# Final_Project.net
KiCad netlist of a schematic drawn in EAGLE
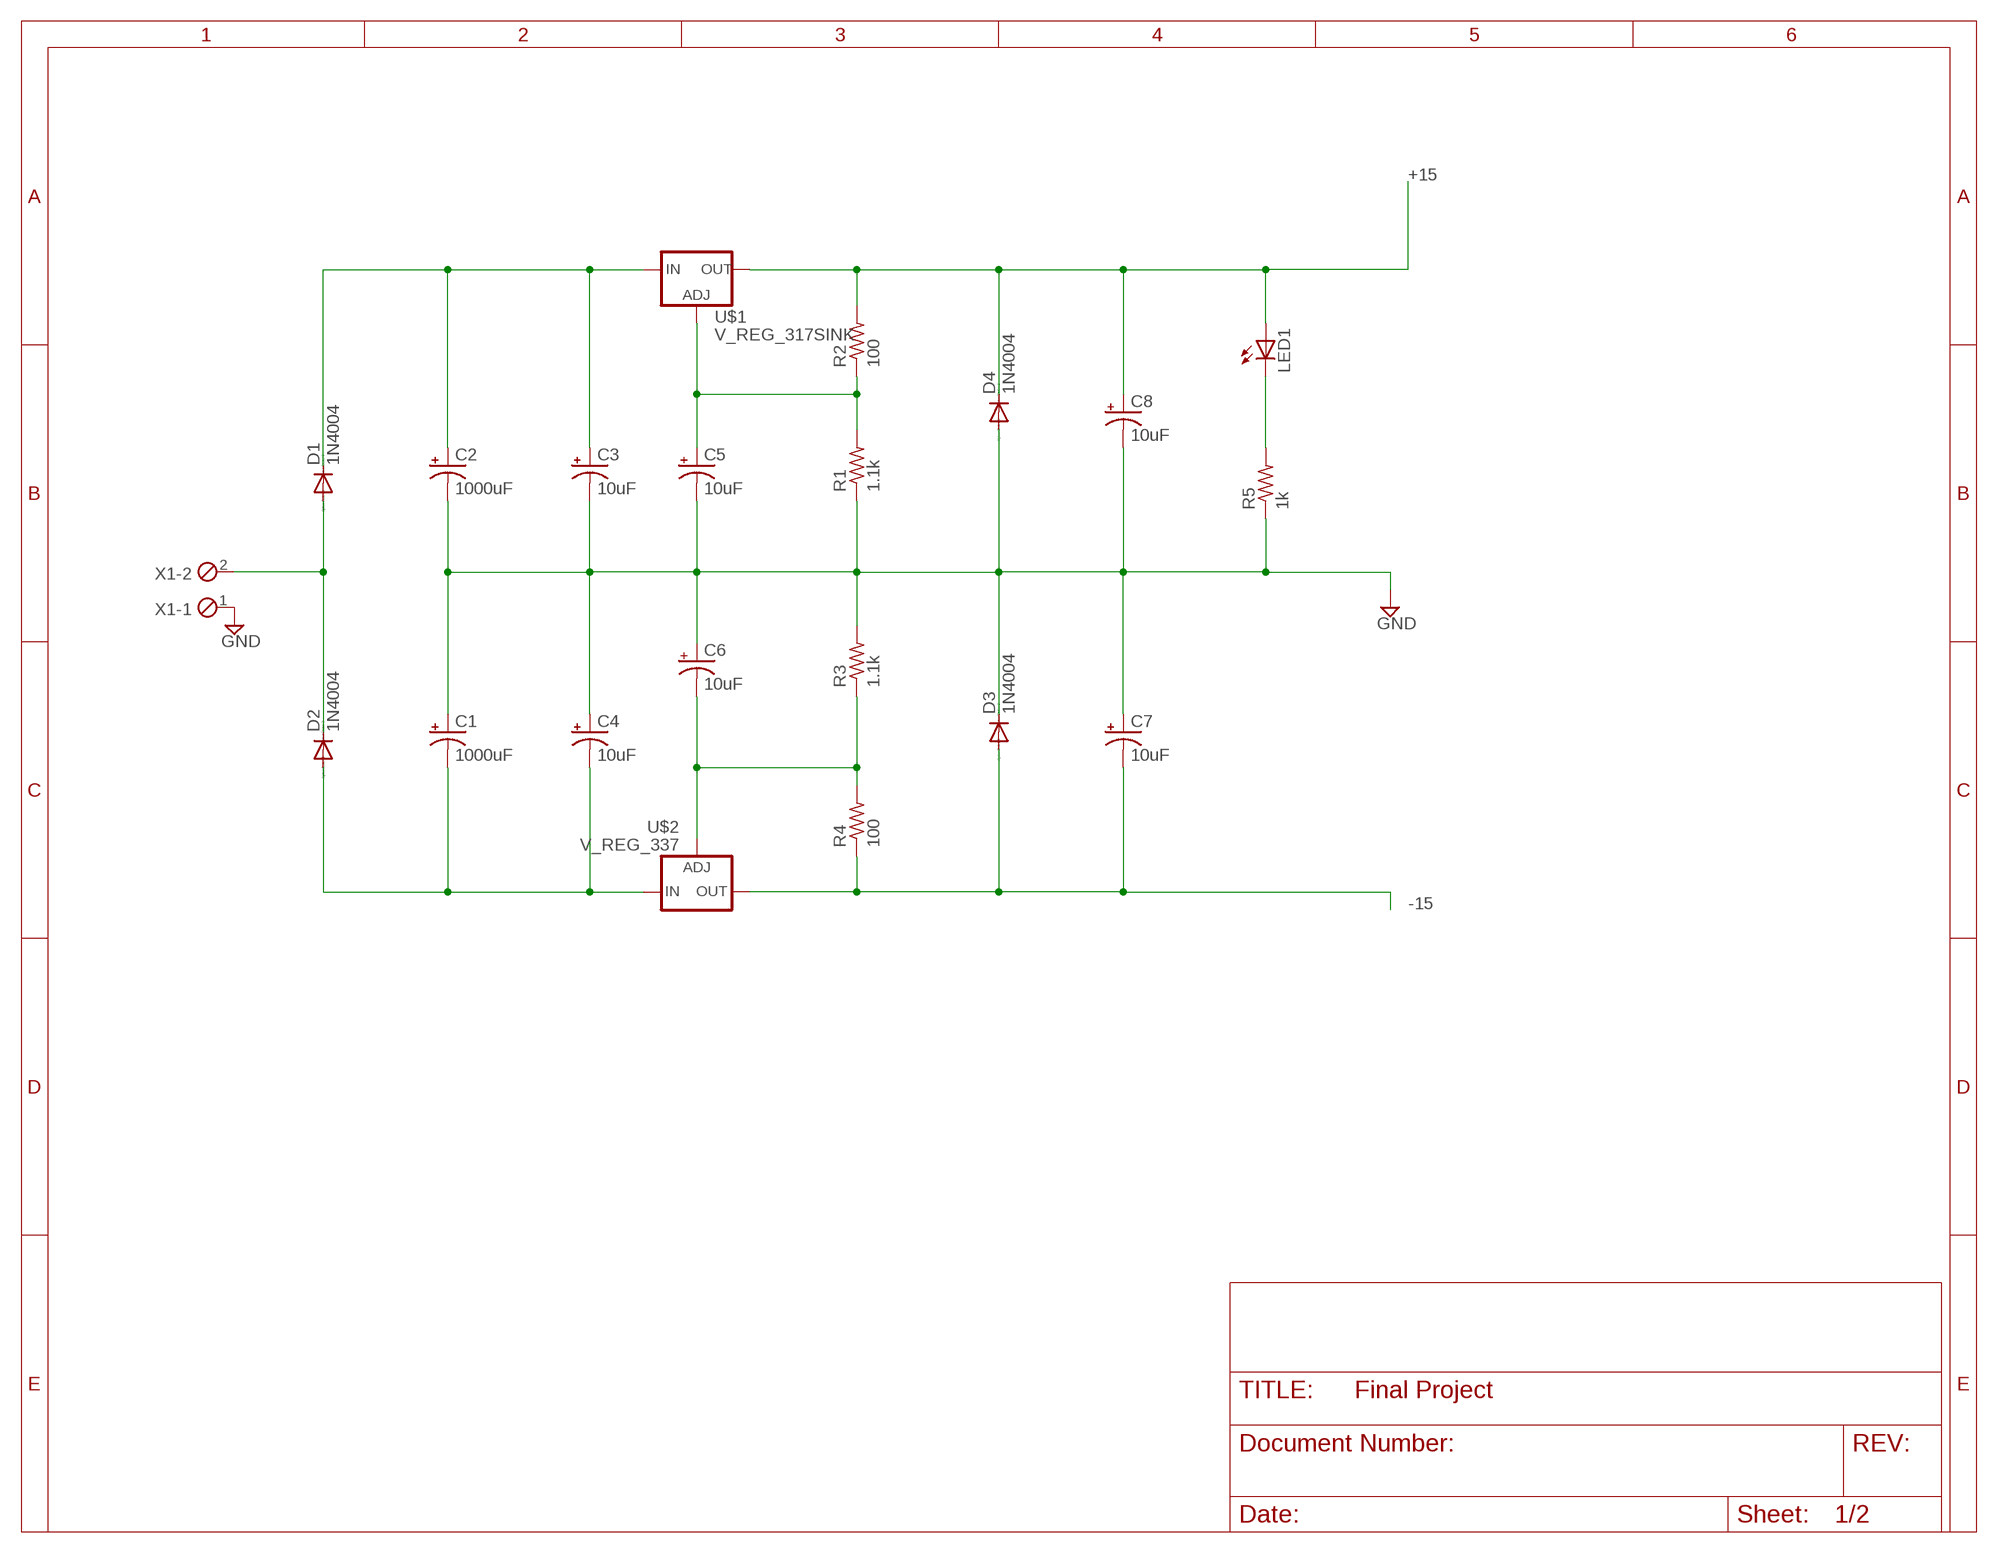
[diagram p0: schematic, sheet 1]
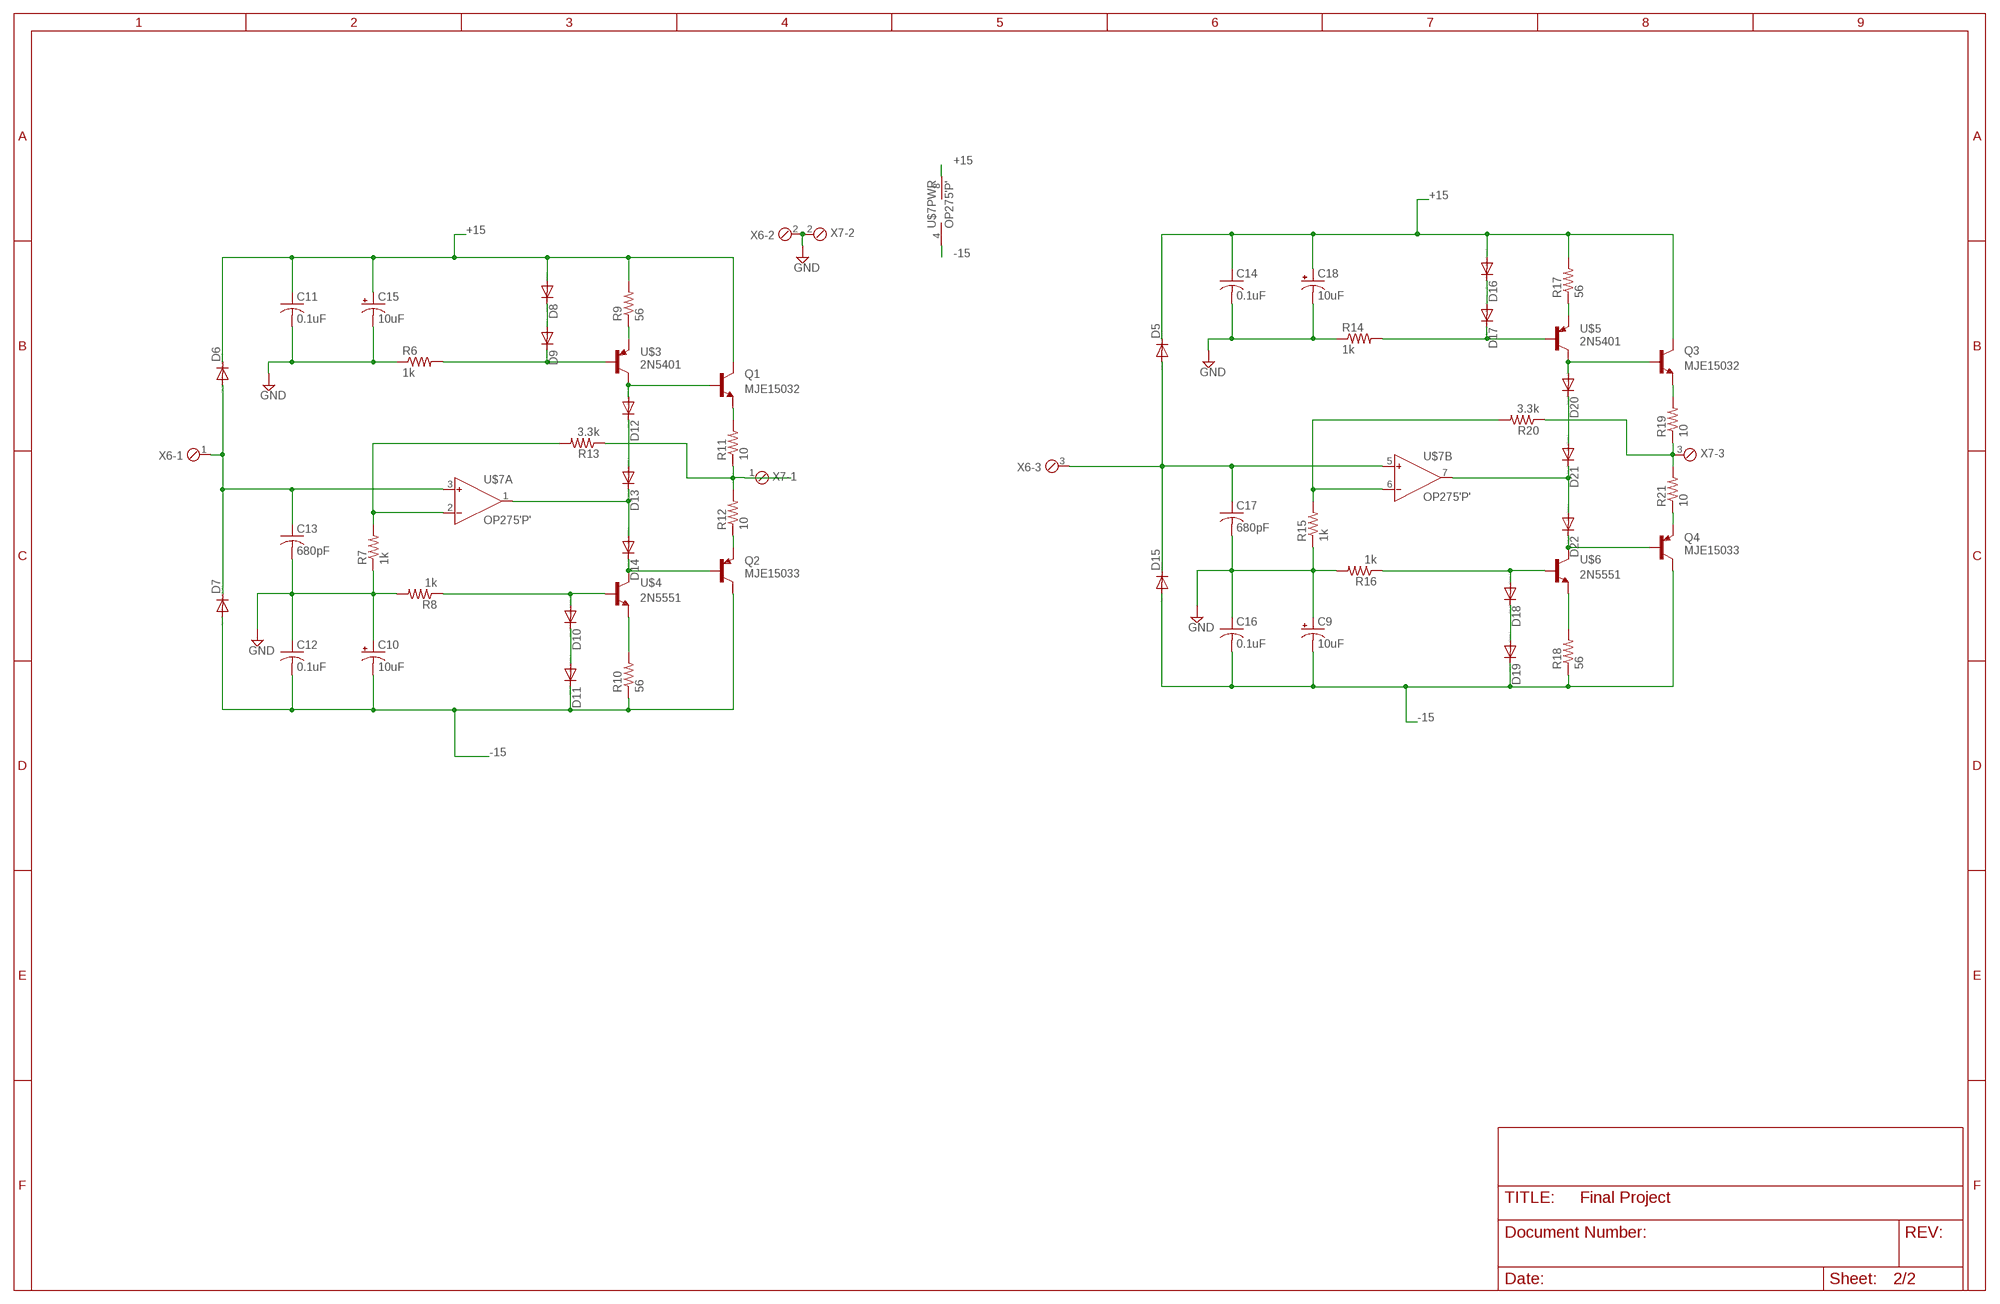
[diagram p1: schematic, sheet 2]

(export (version "E")
  (design (tool "Eeschema 10.0.6"))
  (components
    (comp (ref "C1")
      (value "1000uF")
      (footprint "eagle-import:E5-10,5")
      (libsource (lib "eagle-import") (part "CPOL-USE5-10.5"))
    )
    (comp (ref "C2")
      (value "1000uF")
      (footprint "eagle-import:E5-10,5")
      (libsource (lib "eagle-import") (part "CPOL-USE5-10.5"))
    )
    (comp (ref "C3")
      (value "10uF")
      (footprint "eagle-import:E2-5")
      (libsource (lib "eagle-import") (part "rcl_334_CPOL-USE2-5"))
    )
    (comp (ref "C4")
      (value "10uF")
      (footprint "eagle-import:E2-5")
      (libsource (lib "eagle-import") (part "rcl_334_CPOL-USE2-5"))
    )
    (comp (ref "C5")
      (value "10uF")
      (footprint "eagle-import:E2-5")
      (libsource (lib "eagle-import") (part "rcl_334_CPOL-USE2-5"))
    )
    (comp (ref "C6")
      (value "10uF")
      (footprint "eagle-import:E2-5")
      (libsource (lib "eagle-import") (part "rcl_334_CPOL-USE2-5"))
    )
    (comp (ref "C7")
      (value "10uF")
      (footprint "eagle-import:E2-5")
      (libsource (lib "eagle-import") (part "rcl_334_CPOL-USE2-5"))
    )
    (comp (ref "C8")
      (value "10uF")
      (footprint "eagle-import:E2-5")
      (libsource (lib "eagle-import") (part "rcl_334_CPOL-USE2-5"))
    )
    (comp (ref "D1")
      (value "1N4004")
      (footprint "eagle-import:DO41-10")
      (libsource (lib "eagle-import") (part "1N4004"))
    )
    (comp (ref "D2")
      (value "1N4004")
      (footprint "eagle-import:DO41-10")
      (libsource (lib "eagle-import") (part "1N4004"))
    )
    (comp (ref "D3")
      (value "1N4004")
      (footprint "eagle-import:DO41-10")
      (libsource (lib "eagle-import") (part "1N4004"))
    )
    (comp (ref "D4")
      (value "1N4004")
      (footprint "eagle-import:DO41-10")
      (libsource (lib "eagle-import") (part "1N4004"))
    )
    (comp (ref "LED1")
      (value "LED5MM")
      (footprint "eagle-import:LED5MM")
      (libsource (lib "eagle-import") (part "LED5MM"))
    )
    (comp (ref "R1")
      (value "1.1k")
      (footprint "eagle-import:0204_7")
      (libsource (lib "eagle-import") (part "R-US_0204/7"))
    )
    (comp (ref "R2")
      (value "100")
      (footprint "eagle-import:0204_7")
      (libsource (lib "eagle-import") (part "rcl_334_R-US_0204/7"))
    )
    (comp (ref "R3")
      (value "1.1k")
      (footprint "eagle-import:0204_7")
      (libsource (lib "eagle-import") (part "R-US_0204/7"))
    )
    (comp (ref "R4")
      (value "100")
      (footprint "eagle-import:0204_7")
      (libsource (lib "eagle-import") (part "R-US_0204/7"))
    )
    (comp (ref "R5")
      (value "1k")
      (footprint "eagle-import:0204_7")
      (libsource (lib "eagle-import") (part "R-US_0204/7"))
    )
    (comp (ref "U$1")
      (value "V_REG_317SINK")
      (footprint "eagle-import:TO220-ADJ")
      (libsource (lib "eagle-import") (part "V_REG_317SINK"))
    )
    (comp (ref "U$2")
      (value "V_REG_337")
      (footprint "eagle-import:TO220-ADJ-NEG")
      (libsource (lib "eagle-import") (part "V_REG_337"))
    )
    (comp (ref "X1")
      (value "MPT2")
      (footprint "eagle-import:2POL254")
      (libsource (lib "eagle-import") (part "MPT2"))
    )
    (comp (ref "C9")
      (value "10uF")
      (footprint "eagle-import:E2-5")
      (libsource (lib "eagle-import") (part "rcl_334_CPOL-USE2-5"))
    )
    (comp (ref "C10")
      (value "10uF")
      (footprint "eagle-import:E2-5")
      (libsource (lib "eagle-import") (part "rcl_334_CPOL-USE2-5"))
    )
    (comp (ref "C11")
      (value "0.1uF")
      (footprint "eagle-import:C025-025X050")
      (libsource (lib "eagle-import") (part "C-US025-025X050"))
    )
    (comp (ref "C12")
      (value "0.1uF")
      (footprint "eagle-import:C025-025X050")
      (libsource (lib "eagle-import") (part "C-US025-025X050"))
    )
    (comp (ref "C13")
      (value "680pF")
      (footprint "eagle-import:C025-025X050")
      (libsource (lib "eagle-import") (part "C-US025-025X050"))
    )
    (comp (ref "C14")
      (value "0.1uF")
      (footprint "eagle-import:C025-025X050")
      (libsource (lib "eagle-import") (part "C-US025-025X050"))
    )
    (comp (ref "C15")
      (value "10uF")
      (footprint "eagle-import:E2-5")
      (libsource (lib "eagle-import") (part "rcl_334_CPOL-USE2-5"))
    )
    (comp (ref "C16")
      (value "0.1uF")
      (footprint "eagle-import:C025-025X050")
      (libsource (lib "eagle-import") (part "C-US025-025X050"))
    )
    (comp (ref "C17")
      (value "680pF")
      (footprint "eagle-import:C025-025X050")
      (libsource (lib "eagle-import") (part "C-US025-025X050"))
    )
    (comp (ref "C18")
      (value "10uF")
      (footprint "eagle-import:E2-5")
      (libsource (lib "eagle-import") (part "rcl_334_CPOL-USE2-5"))
    )
    (comp (ref "D5")
      (value "1N4148DO35-10")
      (footprint "eagle-import:DO35-10")
      (libsource (lib "eagle-import") (part "1N4148DO35-10"))
    )
    (comp (ref "D6")
      (value "1N4148DO35-10")
      (footprint "eagle-import:DO35-10")
      (libsource (lib "eagle-import") (part "1N4148DO35-10"))
    )
    (comp (ref "D7")
      (value "1N4148DO35-10")
      (footprint "eagle-import:DO35-10")
      (libsource (lib "eagle-import") (part "1N4148DO35-10"))
    )
    (comp (ref "D8")
      (value "1N4148DO35-10")
      (footprint "eagle-import:DO35-10")
      (libsource (lib "eagle-import") (part "1N4148DO35-10"))
    )
    (comp (ref "D9")
      (value "1N4148DO35-10")
      (footprint "eagle-import:DO35-10")
      (libsource (lib "eagle-import") (part "1N4148DO35-10"))
    )
    (comp (ref "D10")
      (value "1N4148DO35-10")
      (footprint "eagle-import:DO35-10")
      (libsource (lib "eagle-import") (part "1N4148DO35-10"))
    )
    (comp (ref "D11")
      (value "1N4148DO35-10")
      (footprint "eagle-import:DO35-10")
      (libsource (lib "eagle-import") (part "1N4148DO35-10"))
    )
    (comp (ref "D12")
      (value "1N4148DO35-10")
      (footprint "eagle-import:DO35-10")
      (libsource (lib "eagle-import") (part "1N4148DO35-10"))
    )
    (comp (ref "D13")
      (value "1N4148DO35-10")
      (footprint "eagle-import:DO35-10")
      (libsource (lib "eagle-import") (part "1N4148DO35-10"))
    )
    (comp (ref "D14")
      (value "1N4148DO35-10")
      (footprint "eagle-import:DO35-10")
      (libsource (lib "eagle-import") (part "1N4148DO35-10"))
    )
    (comp (ref "D15")
      (value "1N4148DO35-10")
      (footprint "eagle-import:DO35-10")
      (libsource (lib "eagle-import") (part "1N4148DO35-10"))
    )
    (comp (ref "D16")
      (value "1N4148DO35-10")
      (footprint "eagle-import:DO35-10")
      (libsource (lib "eagle-import") (part "1N4148DO35-10"))
    )
    (comp (ref "D17")
      (value "1N4148DO35-10")
      (footprint "eagle-import:DO35-10")
      (libsource (lib "eagle-import") (part "1N4148DO35-10"))
    )
    (comp (ref "D18")
      (value "1N4148DO35-10")
      (footprint "eagle-import:DO35-10")
      (libsource (lib "eagle-import") (part "1N4148DO35-10"))
    )
    (comp (ref "D19")
      (value "1N4148DO35-10")
      (footprint "eagle-import:DO35-10")
      (libsource (lib "eagle-import") (part "1N4148DO35-10"))
    )
    (comp (ref "D20")
      (value "1N4148DO35-10")
      (footprint "eagle-import:DO35-10")
      (libsource (lib "eagle-import") (part "1N4148DO35-10"))
    )
    (comp (ref "D21")
      (value "1N4148DO35-10")
      (footprint "eagle-import:DO35-10")
      (libsource (lib "eagle-import") (part "1N4148DO35-10"))
    )
    (comp (ref "D22")
      (value "1N4148DO35-10")
      (footprint "eagle-import:DO35-10")
      (libsource (lib "eagle-import") (part "1N4148DO35-10"))
    )
    (comp (ref "Q1")
      (value "MJE15032")
      (footprint "eagle-import:TO220V")
      (libsource (lib "eagle-import") (part "MJE15032"))
    )
    (comp (ref "Q2")
      (value "MJE15033")
      (footprint "eagle-import:TO220V")
      (libsource (lib "eagle-import") (part "MJE15033"))
    )
    (comp (ref "Q3")
      (value "MJE15032")
      (footprint "eagle-import:TO220V")
      (libsource (lib "eagle-import") (part "MJE15032"))
    )
    (comp (ref "Q4")
      (value "MJE15033")
      (footprint "eagle-import:TO220V")
      (libsource (lib "eagle-import") (part "MJE15033"))
    )
    (comp (ref "R6")
      (value "1k")
      (footprint "eagle-import:0204_7")
      (libsource (lib "eagle-import") (part "rcl_334_R-US_0204/7"))
    )
    (comp (ref "R7")
      (value "1k")
      (footprint "eagle-import:0204_7")
      (libsource (lib "eagle-import") (part "rcl_334_R-US_0204/7"))
    )
    (comp (ref "R8")
      (value "1k")
      (footprint "eagle-import:0204_7")
      (libsource (lib "eagle-import") (part "rcl_334_R-US_0204/7"))
    )
    (comp (ref "R9")
      (value "56")
      (footprint "eagle-import:0204_7")
      (libsource (lib "eagle-import") (part "rcl_334_R-US_0204/7"))
    )
    (comp (ref "R10")
      (value "56")
      (footprint "eagle-import:0204_7")
      (libsource (lib "eagle-import") (part "rcl_334_R-US_0204/7"))
    )
    (comp (ref "R11")
      (value "10")
      (footprint "eagle-import:0204_7")
      (libsource (lib "eagle-import") (part "rcl_334_R-US_0204/7"))
    )
    (comp (ref "R12")
      (value "10")
      (footprint "eagle-import:0204_7")
      (libsource (lib "eagle-import") (part "rcl_334_R-US_0204/7"))
    )
    (comp (ref "R13")
      (value "3.3k")
      (footprint "eagle-import:0204_7")
      (libsource (lib "eagle-import") (part "rcl_334_R-US_0204/7"))
    )
    (comp (ref "R14")
      (value "1k")
      (footprint "eagle-import:0204_7")
      (libsource (lib "eagle-import") (part "rcl_334_R-US_0204/7"))
    )
    (comp (ref "R15")
      (value "1k")
      (footprint "eagle-import:0204_7")
      (libsource (lib "eagle-import") (part "rcl_334_R-US_0204/7"))
    )
    (comp (ref "R16")
      (value "1k")
      (footprint "eagle-import:0204_7")
      (libsource (lib "eagle-import") (part "rcl_334_R-US_0204/7"))
    )
    (comp (ref "R17")
      (value "56")
      (footprint "eagle-import:0204_7")
      (libsource (lib "eagle-import") (part "rcl_334_R-US_0204/7"))
    )
    (comp (ref "R18")
      (value "56")
      (footprint "eagle-import:0204_7")
      (libsource (lib "eagle-import") (part "rcl_334_R-US_0204/7"))
    )
    (comp (ref "R19")
      (value "10")
      (footprint "eagle-import:0204_7")
      (libsource (lib "eagle-import") (part "rcl_334_R-US_0204/7"))
    )
    (comp (ref "R20")
      (value "3.3k")
      (footprint "eagle-import:0204_7")
      (libsource (lib "eagle-import") (part "rcl_334_R-US_0204/7"))
    )
    (comp (ref "R21")
      (value "10")
      (footprint "eagle-import:0204_7")
      (libsource (lib "eagle-import") (part "rcl_334_R-US_0204/7"))
    )
    (comp (ref "U$3")
      (value "2N5401")
      (footprint "eagle-import:2N5401")
      (libsource (lib "eagle-import") (part "2N5401"))
    )
    (comp (ref "U$4")
      (value "2N5551")
      (footprint "eagle-import:2N5551")
      (libsource (lib "eagle-import") (part "2N5551"))
    )
    (comp (ref "U$5")
      (value "2N5401")
      (footprint "eagle-import:2N5401")
      (libsource (lib "eagle-import") (part "2N5401"))
    )
    (comp (ref "U$6")
      (value "2N5551")
      (footprint "eagle-import:2N5551")
      (libsource (lib "eagle-import") (part "2N5551"))
    )
    (comp (ref "U$7")
      (value "OP275'P'")
      (footprint "eagle-import:DIL08")
      (libsource (lib "eagle-import") (part "OP275'P'"))
    )
    (comp (ref "X6")
      (value "MPT3")
      (footprint "eagle-import:3POL254")
      (libsource (lib "eagle-import") (part "MPT3"))
    )
    (comp (ref "X7")
      (value "MPT3")
      (footprint "eagle-import:3POL254")
      (libsource (lib "eagle-import") (part "MPT3"))
    )
  )
  (nets
    (net (code "1") (name "+15") (class "Default")
      (node (ref "C11") (pin "1") (pinfunction "1_1") (pintype "passive"))
      (node (ref "C14") (pin "1") (pinfunction "1_1") (pintype "passive"))
      (node (ref "C15") (pin "+") (pinfunction "+_+") (pintype "passive"))
      (node (ref "C18") (pin "+") (pinfunction "+_+") (pintype "passive"))
      (node (ref "C8") (pin "+") (pinfunction "+_+") (pintype "passive"))
      (node (ref "D16") (pin "A") (pinfunction "A_A") (pintype "passive"))
      (node (ref "D4") (pin "C") (pinfunction "C_C") (pintype "passive"))
      (node (ref "D5") (pin "C") (pinfunction "C_C") (pintype "passive"))
      (node (ref "D6") (pin "C") (pinfunction "C_C") (pintype "passive"))
      (node (ref "D8") (pin "A") (pinfunction "A_A") (pintype "passive"))
      (node (ref "LED1") (pin "A") (pinfunction "A_A") (pintype "passive"))
      (node (ref "Q1") (pin "2") (pinfunction "C_2") (pintype "passive"))
      (node (ref "Q3") (pin "2") (pinfunction "C_2") (pintype "passive"))
      (node (ref "R17") (pin "2") (pinfunction "2_2") (pintype "passive"))
      (node (ref "R2") (pin "2") (pinfunction "2_2") (pintype "passive"))
      (node (ref "R9") (pin "2") (pinfunction "2_2") (pintype "passive"))
      (node (ref "U$1") (pin "OUT") (pinfunction "OUT_OUT") (pintype "output"))
      (node (ref "U$7") (pin "8") (pinfunction "V+_8") (pintype "power_in"))
    )
    (net (code "2") (name "-15") (class "Default")
      (node (ref "C10") (pin "-") (pinfunction "-_-") (pintype "passive"))
      (node (ref "C12") (pin "2") (pinfunction "2_2") (pintype "passive"))
      (node (ref "C16") (pin "2") (pinfunction "2_2") (pintype "passive"))
      (node (ref "C7") (pin "-") (pinfunction "-_-") (pintype "passive"))
      (node (ref "C9") (pin "-") (pinfunction "-_-") (pintype "passive"))
      (node (ref "D11") (pin "C") (pinfunction "C_C") (pintype "passive"))
      (node (ref "D15") (pin "A") (pinfunction "A_A") (pintype "passive"))
      (node (ref "D19") (pin "C") (pinfunction "C_C") (pintype "passive"))
      (node (ref "D3") (pin "A") (pinfunction "A_A") (pintype "passive"))
      (node (ref "D7") (pin "A") (pinfunction "A_A") (pintype "passive"))
      (node (ref "Q2") (pin "2") (pinfunction "C_2") (pintype "passive"))
      (node (ref "Q4") (pin "2") (pinfunction "C_2") (pintype "passive"))
      (node (ref "R10") (pin "1") (pinfunction "1_1") (pintype "passive"))
      (node (ref "R18") (pin "1") (pinfunction "1_1") (pintype "passive"))
      (node (ref "R4") (pin "1") (pinfunction "1_1") (pintype "passive"))
      (node (ref "U$2") (pin "OUT") (pinfunction "OUT_OUT") (pintype "output"))
      (node (ref "U$7") (pin "4") (pinfunction "V-_4") (pintype "power_in"))
    )
    (net (code "3") (name "GND") (class "Default")
      (node (ref "C1") (pin "+") (pinfunction "+_+") (pintype "passive"))
      (node (ref "C10") (pin "+") (pinfunction "+_+") (pintype "passive"))
      (node (ref "C11") (pin "2") (pinfunction "2_2") (pintype "passive"))
      (node (ref "C12") (pin "1") (pinfunction "1_1") (pintype "passive"))
      (node (ref "C13") (pin "2") (pinfunction "2_2") (pintype "passive"))
      (node (ref "C14") (pin "2") (pinfunction "2_2") (pintype "passive"))
      (node (ref "C15") (pin "-") (pinfunction "-_-") (pintype "passive"))
      (node (ref "C16") (pin "1") (pinfunction "1_1") (pintype "passive"))
      (node (ref "C17") (pin "2") (pinfunction "2_2") (pintype "passive"))
      (node (ref "C18") (pin "-") (pinfunction "-_-") (pintype "passive"))
      (node (ref "C2") (pin "-") (pinfunction "-_-") (pintype "passive"))
      (node (ref "C3") (pin "-") (pinfunction "-_-") (pintype "passive"))
      (node (ref "C4") (pin "+") (pinfunction "+_+") (pintype "passive"))
      (node (ref "C5") (pin "-") (pinfunction "-_-") (pintype "passive"))
      (node (ref "C6") (pin "+") (pinfunction "+_+") (pintype "passive"))
      (node (ref "C7") (pin "+") (pinfunction "+_+") (pintype "passive"))
      (node (ref "C8") (pin "-") (pinfunction "-_-") (pintype "passive"))
      (node (ref "C9") (pin "+") (pinfunction "+_+") (pintype "passive"))
      (node (ref "D3") (pin "C") (pinfunction "C_C") (pintype "passive"))
      (node (ref "D4") (pin "A") (pinfunction "A_A") (pintype "passive"))
      (node (ref "R1") (pin "1") (pinfunction "1_1") (pintype "passive"))
      (node (ref "R14") (pin "1") (pinfunction "1_1") (pintype "passive"))
      (node (ref "R15") (pin "1") (pinfunction "1_1") (pintype "passive"))
      (node (ref "R16") (pin "2") (pinfunction "2_2") (pintype "passive"))
      (node (ref "R3") (pin "2") (pinfunction "2_2") (pintype "passive"))
      (node (ref "R5") (pin "1") (pinfunction "1_1") (pintype "passive"))
      (node (ref "R6") (pin "1") (pinfunction "1_1") (pintype "passive"))
      (node (ref "R7") (pin "1") (pinfunction "1_1") (pintype "passive"))
      (node (ref "R8") (pin "2") (pinfunction "2_2") (pintype "passive"))
      (node (ref "X1") (pin "1") (pinfunction "1_1") (pintype "passive"))
      (node (ref "X6") (pin "2") (pinfunction "1_2") (pintype "passive"))
      (node (ref "X7") (pin "2") (pinfunction "1_2") (pintype "passive"))
    )
    (net (code "4") (name "Net-(C1-Pad-)") (class "Default")
      (node (ref "C1") (pin "-") (pinfunction "-_-") (pintype "passive"))
      (node (ref "C4") (pin "-") (pinfunction "-_-") (pintype "passive"))
      (node (ref "D2") (pin "A") (pinfunction "A_A") (pintype "passive"))
      (node (ref "U$2") (pin "IN") (pinfunction "IN_IN") (pintype "input"))
    )
    (net (code "5") (name "Net-(C2-Pad+)") (class "Default")
      (node (ref "C2") (pin "+") (pinfunction "+_+") (pintype "passive"))
      (node (ref "C3") (pin "+") (pinfunction "+_+") (pintype "passive"))
      (node (ref "D1") (pin "C") (pinfunction "C_C") (pintype "passive"))
      (node (ref "U$1") (pin "IN") (pinfunction "IN_IN") (pintype "input"))
    )
    (net (code "6") (name "Net-(C5-Pad+)") (class "Default")
      (node (ref "C5") (pin "+") (pinfunction "+_+") (pintype "passive"))
      (node (ref "R1") (pin "2") (pinfunction "2_2") (pintype "passive"))
      (node (ref "R2") (pin "1") (pinfunction "1_1") (pintype "passive"))
      (node (ref "U$1") (pin "ADJ") (pinfunction "ADJ_ADJ") (pintype "input"))
    )
    (net (code "7") (name "Net-(C6-Pad-)") (class "Default")
      (node (ref "C6") (pin "-") (pinfunction "-_-") (pintype "passive"))
      (node (ref "R3") (pin "1") (pinfunction "1_1") (pintype "passive"))
      (node (ref "R4") (pin "2") (pinfunction "2_2") (pintype "passive"))
      (node (ref "U$2") (pin "ADJ") (pinfunction "ADJ_ADJ") (pintype "input"))
    )
    (net (code "8") (name "Net-(D8-PadC)") (class "Default")
      (node (ref "D8") (pin "C") (pinfunction "C_C") (pintype "passive"))
      (node (ref "D9") (pin "A") (pinfunction "A_A") (pintype "passive"))
    )
    (net (code "9") (name "Net-(D9-PadC)") (class "Default")
      (node (ref "D9") (pin "C") (pinfunction "C_C") (pintype "passive"))
      (node (ref "R6") (pin "2") (pinfunction "2_2") (pintype "passive"))
      (node (ref "U$3") (pin "B") (pinfunction "B_B") (pintype "passive"))
    )
    (net (code "10") (name "Net-(D10-PadA)") (class "Default")
      (node (ref "D10") (pin "A") (pinfunction "A_A") (pintype "passive"))
      (node (ref "R8") (pin "1") (pinfunction "1_1") (pintype "passive"))
      (node (ref "U$4") (pin "B") (pinfunction "B_B") (pintype "passive"))
    )
    (net (code "11") (name "Net-(D10-PadC)") (class "Default")
      (node (ref "D10") (pin "C") (pinfunction "C_C") (pintype "passive"))
      (node (ref "D11") (pin "A") (pinfunction "A_A") (pintype "passive"))
    )
    (net (code "12") (name "Net-(D12-PadC)") (class "Default")
      (node (ref "D12") (pin "C") (pinfunction "C_C") (pintype "passive"))
      (node (ref "D13") (pin "A") (pinfunction "A_A") (pintype "passive"))
    )
    (net (code "13") (name "Net-(D16-PadC)") (class "Default")
      (node (ref "D16") (pin "C") (pinfunction "C_C") (pintype "passive"))
      (node (ref "D17") (pin "A") (pinfunction "A_A") (pintype "passive"))
    )
    (net (code "14") (name "Net-(D17-PadC)") (class "Default")
      (node (ref "D17") (pin "C") (pinfunction "C_C") (pintype "passive"))
      (node (ref "R14") (pin "2") (pinfunction "2_2") (pintype "passive"))
      (node (ref "U$5") (pin "B") (pinfunction "B_B") (pintype "passive"))
    )
    (net (code "15") (name "Net-(D18-PadA)") (class "Default")
      (node (ref "D18") (pin "A") (pinfunction "A_A") (pintype "passive"))
      (node (ref "R16") (pin "1") (pinfunction "1_1") (pintype "passive"))
      (node (ref "U$6") (pin "B") (pinfunction "B_B") (pintype "passive"))
    )
    (net (code "16") (name "Net-(D18-PadC)") (class "Default")
      (node (ref "D18") (pin "C") (pinfunction "C_C") (pintype "passive"))
      (node (ref "D19") (pin "A") (pinfunction "A_A") (pintype "passive"))
    )
    (net (code "17") (name "Net-(D20-PadC)") (class "Default")
      (node (ref "D20") (pin "C") (pinfunction "C_C") (pintype "passive"))
      (node (ref "D21") (pin "A") (pinfunction "A_A") (pintype "passive"))
    )
    (net (code "18") (name "Net-(LED1-C)") (class "Default")
      (node (ref "LED1") (pin "K") (pinfunction "C_K") (pintype "passive"))
      (node (ref "R5") (pin "2") (pinfunction "2_2") (pintype "passive"))
    )
    (net (code "19") (name "Net-(Q1-B)") (class "Default")
      (node (ref "D12") (pin "A") (pinfunction "A_A") (pintype "passive"))
      (node (ref "Q1") (pin "1") (pinfunction "B_1") (pintype "passive"))
      (node (ref "U$3") (pin "C") (pinfunction "C_C") (pintype "passive"))
    )
    (net (code "20") (name "Net-(Q1-E)") (class "Default")
      (node (ref "Q1") (pin "3") (pinfunction "E_3") (pintype "passive"))
      (node (ref "R11") (pin "2") (pinfunction "2_2") (pintype "passive"))
    )
    (net (code "21") (name "Net-(Q2-B)") (class "Default")
      (node (ref "D14") (pin "C") (pinfunction "C_C") (pintype "passive"))
      (node (ref "Q2") (pin "1") (pinfunction "B_1") (pintype "passive"))
      (node (ref "U$4") (pin "C") (pinfunction "C_C") (pintype "passive"))
    )
    (net (code "22") (name "Net-(Q2-E)") (class "Default")
      (node (ref "Q2") (pin "3") (pinfunction "E_3") (pintype "passive"))
      (node (ref "R12") (pin "1") (pinfunction "1_1") (pintype "passive"))
    )
    (net (code "23") (name "Net-(Q3-B)") (class "Default")
      (node (ref "D20") (pin "A") (pinfunction "A_A") (pintype "passive"))
      (node (ref "Q3") (pin "1") (pinfunction "B_1") (pintype "passive"))
      (node (ref "U$5") (pin "C") (pinfunction "C_C") (pintype "passive"))
    )
    (net (code "24") (name "Net-(Q3-E)") (class "Default")
      (node (ref "Q3") (pin "3") (pinfunction "E_3") (pintype "passive"))
      (node (ref "R19") (pin "2") (pinfunction "2_2") (pintype "passive"))
    )
    (net (code "25") (name "Net-(Q4-B)") (class "Default")
      (node (ref "D22") (pin "C") (pinfunction "C_C") (pintype "passive"))
      (node (ref "Q4") (pin "1") (pinfunction "B_1") (pintype "passive"))
      (node (ref "U$6") (pin "C") (pinfunction "C_C") (pintype "passive"))
    )
    (net (code "26") (name "Net-(Q4-E)") (class "Default")
      (node (ref "Q4") (pin "3") (pinfunction "E_3") (pintype "passive"))
      (node (ref "R21") (pin "1") (pinfunction "1_1") (pintype "passive"))
    )
    (net (code "27") (name "Net-(R9-Pad1)") (class "Default")
      (node (ref "R9") (pin "1") (pinfunction "1_1") (pintype "passive"))
      (node (ref "U$3") (pin "E") (pinfunction "E_E") (pintype "passive"))
    )
    (net (code "28") (name "Net-(R10-Pad2)") (class "Default")
      (node (ref "R10") (pin "2") (pinfunction "2_2") (pintype "passive"))
      (node (ref "U$4") (pin "E") (pinfunction "E_E") (pintype "passive"))
    )
    (net (code "29") (name "Net-(R11-Pad1)") (class "Default")
      (node (ref "R11") (pin "1") (pinfunction "1_1") (pintype "passive"))
      (node (ref "R12") (pin "2") (pinfunction "2_2") (pintype "passive"))
      (node (ref "R13") (pin "1") (pinfunction "1_1") (pintype "passive"))
      (node (ref "X7") (pin "1") (pinfunction "1_1") (pintype "passive"))
    )
    (net (code "30") (name "Net-(R17-Pad1)") (class "Default")
      (node (ref "R17") (pin "1") (pinfunction "1_1") (pintype "passive"))
      (node (ref "U$5") (pin "E") (pinfunction "E_E") (pintype "passive"))
    )
    (net (code "31") (name "Net-(R18-Pad2)") (class "Default")
      (node (ref "R18") (pin "2") (pinfunction "2_2") (pintype "passive"))
      (node (ref "U$6") (pin "E") (pinfunction "E_E") (pintype "passive"))
    )
    (net (code "32") (name "Net-(U$7A-IN+)") (class "Default")
      (node (ref "C13") (pin "1") (pinfunction "1_1") (pintype "passive"))
      (node (ref "D6") (pin "A") (pinfunction "A_A") (pintype "passive"))
      (node (ref "D7") (pin "C") (pinfunction "C_C") (pintype "passive"))
      (node (ref "U$7") (pin "3") (pinfunction "IN+_3") (pintype "input"))
      (node (ref "X6") (pin "1") (pinfunction "1_1") (pintype "passive"))
    )
    (net (code "33") (name "Net-(U$7A-IN-)") (class "Default")
      (node (ref "R13") (pin "2") (pinfunction "2_2") (pintype "passive"))
      (node (ref "R7") (pin "2") (pinfunction "2_2") (pintype "passive"))
      (node (ref "U$7") (pin "2") (pinfunction "IN-_2") (pintype "input"))
    )
    (net (code "34") (name "Net-(U$7A-OUT)") (class "Default")
      (node (ref "D13") (pin "C") (pinfunction "C_C") (pintype "passive"))
      (node (ref "D14") (pin "A") (pinfunction "A_A") (pintype "passive"))
      (node (ref "U$7") (pin "1") (pinfunction "OUT_1") (pintype "output"))
    )
    (net (code "35") (name "Net-(U$7B-IN+)") (class "Default")
      (node (ref "C17") (pin "1") (pinfunction "1_1") (pintype "passive"))
      (node (ref "D15") (pin "C") (pinfunction "C_C") (pintype "passive"))
      (node (ref "D5") (pin "A") (pinfunction "A_A") (pintype "passive"))
      (node (ref "U$7") (pin "5") (pinfunction "IN+_5") (pintype "input"))
      (node (ref "X6") (pin "3") (pinfunction "1_3") (pintype "passive"))
    )
    (net (code "36") (name "Net-(U$7B-IN-)") (class "Default")
      (node (ref "R15") (pin "2") (pinfunction "2_2") (pintype "passive"))
      (node (ref "R20") (pin "2") (pinfunction "2_2") (pintype "passive"))
      (node (ref "U$7") (pin "6") (pinfunction "IN-_6") (pintype "input"))
    )
    (net (code "37") (name "Net-(U$7B-OUT)") (class "Default")
      (node (ref "D21") (pin "C") (pinfunction "C_C") (pintype "passive"))
      (node (ref "D22") (pin "A") (pinfunction "A_A") (pintype "passive"))
      (node (ref "U$7") (pin "7") (pinfunction "OUT_7") (pintype "output"))
    )
    (net (code "38") (name "Net-(X1B-1)") (class "Default")
      (node (ref "D1") (pin "A") (pinfunction "A_A") (pintype "passive"))
      (node (ref "D2") (pin "C") (pinfunction "C_C") (pintype "passive"))
      (node (ref "X1") (pin "2") (pinfunction "1_2") (pintype "passive"))
    )
    (net (code "39") (name "Net-(X7C-1)") (class "Default")
      (node (ref "R19") (pin "1") (pinfunction "1_1") (pintype "passive"))
      (node (ref "R20") (pin "1") (pinfunction "1_1") (pintype "passive"))
      (node (ref "R21") (pin "2") (pinfunction "2_2") (pintype "passive"))
      (node (ref "X7") (pin "3") (pinfunction "1_3") (pintype "passive"))
    )
  )
)
